# 7SegSplitter.net
KiCad netlist of a schematic drawn in Altium Designer
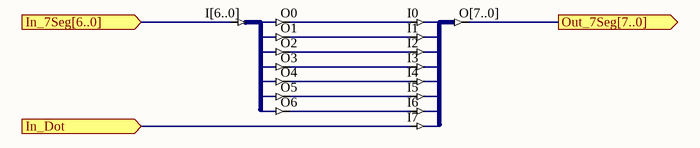
[diagram p0: 7SegSplitter.SchDoc]

(export (version "E")
  (design (tool "Eeschema 10.0.6"))
  (components
    (comp (ref "U110")
      (value "J8S_8B")
      (description "8 Single pin inputs to single 8-Bit output bus")
      (fields (field (name "PUBLISHER") "Altium Limited"))
      (libsource (lib "FPGA Generic") (part "J8S_8B"))
    )
    (comp (ref "U111")
      (value "J7B_7S")
      (description "7-Bit input bus to 7 Single pin outputs")
      (fields (field (name "PUBLISHER") "Altium Limited"))
      (libsource (lib "FPGA Generic") (part "J7B_7S"))
    )
  )
  (nets
    (net (code "16") (name "/In_7Seg[6..0]") (class "Default")
      (node (ref "U111") (pin "I[6..0]") (pinfunction "I[6..0]_I[6..0]") (pintype "input"))
    )
    (net (code "17") (name "/In_Dot") (class "Default")
      (node (ref "U110") (pin "I7") (pinfunction "I7_I7") (pintype "input"))
    )
    (net (code "18") (name "/Out_7Seg[7..0]") (class "Default")
      (node (ref "U110") (pin "O[7..0]") (pinfunction "O[7..0]_O[7..0]") (pintype "output"))
    )
    (net (code "19") (name "Net-(U110-PadI0)") (class "Default")
      (node (ref "U110") (pin "I0") (pinfunction "I0_I0") (pintype "input"))
      (node (ref "U111") (pin "O0") (pinfunction "O0_O0") (pintype "output"))
    )
    (net (code "20") (name "Net-(U110-PadI1)") (class "Default")
      (node (ref "U110") (pin "I1") (pinfunction "I1_I1") (pintype "input"))
      (node (ref "U111") (pin "O1") (pinfunction "O1_O1") (pintype "output"))
    )
    (net (code "21") (name "Net-(U110-PadI2)") (class "Default")
      (node (ref "U110") (pin "I2") (pinfunction "I2_I2") (pintype "input"))
      (node (ref "U111") (pin "O2") (pinfunction "O2_O2") (pintype "output"))
    )
    (net (code "22") (name "Net-(U110-PadI3)") (class "Default")
      (node (ref "U110") (pin "I3") (pinfunction "I3_I3") (pintype "input"))
      (node (ref "U111") (pin "O3") (pinfunction "O3_O3") (pintype "output"))
    )
    (net (code "23") (name "Net-(U110-PadI4)") (class "Default")
      (node (ref "U110") (pin "I4") (pinfunction "I4_I4") (pintype "input"))
      (node (ref "U111") (pin "O4") (pinfunction "O4_O4") (pintype "output"))
    )
    (net (code "24") (name "Net-(U110-PadI5)") (class "Default")
      (node (ref "U110") (pin "I5") (pinfunction "I5_I5") (pintype "input"))
      (node (ref "U111") (pin "O5") (pinfunction "O5_O5") (pintype "output"))
    )
    (net (code "25") (name "Net-(U110-PadI6)") (class "Default")
      (node (ref "U110") (pin "I6") (pinfunction "I6_I6") (pintype "input"))
      (node (ref "U111") (pin "O6") (pinfunction "O6_O6") (pintype "output"))
    )
  )
)
